# ProPrj_ProDocument_IO_Board_v3_1_2024-08.net
KiCad netlist of a schematic drawn in EasyEDA Pro
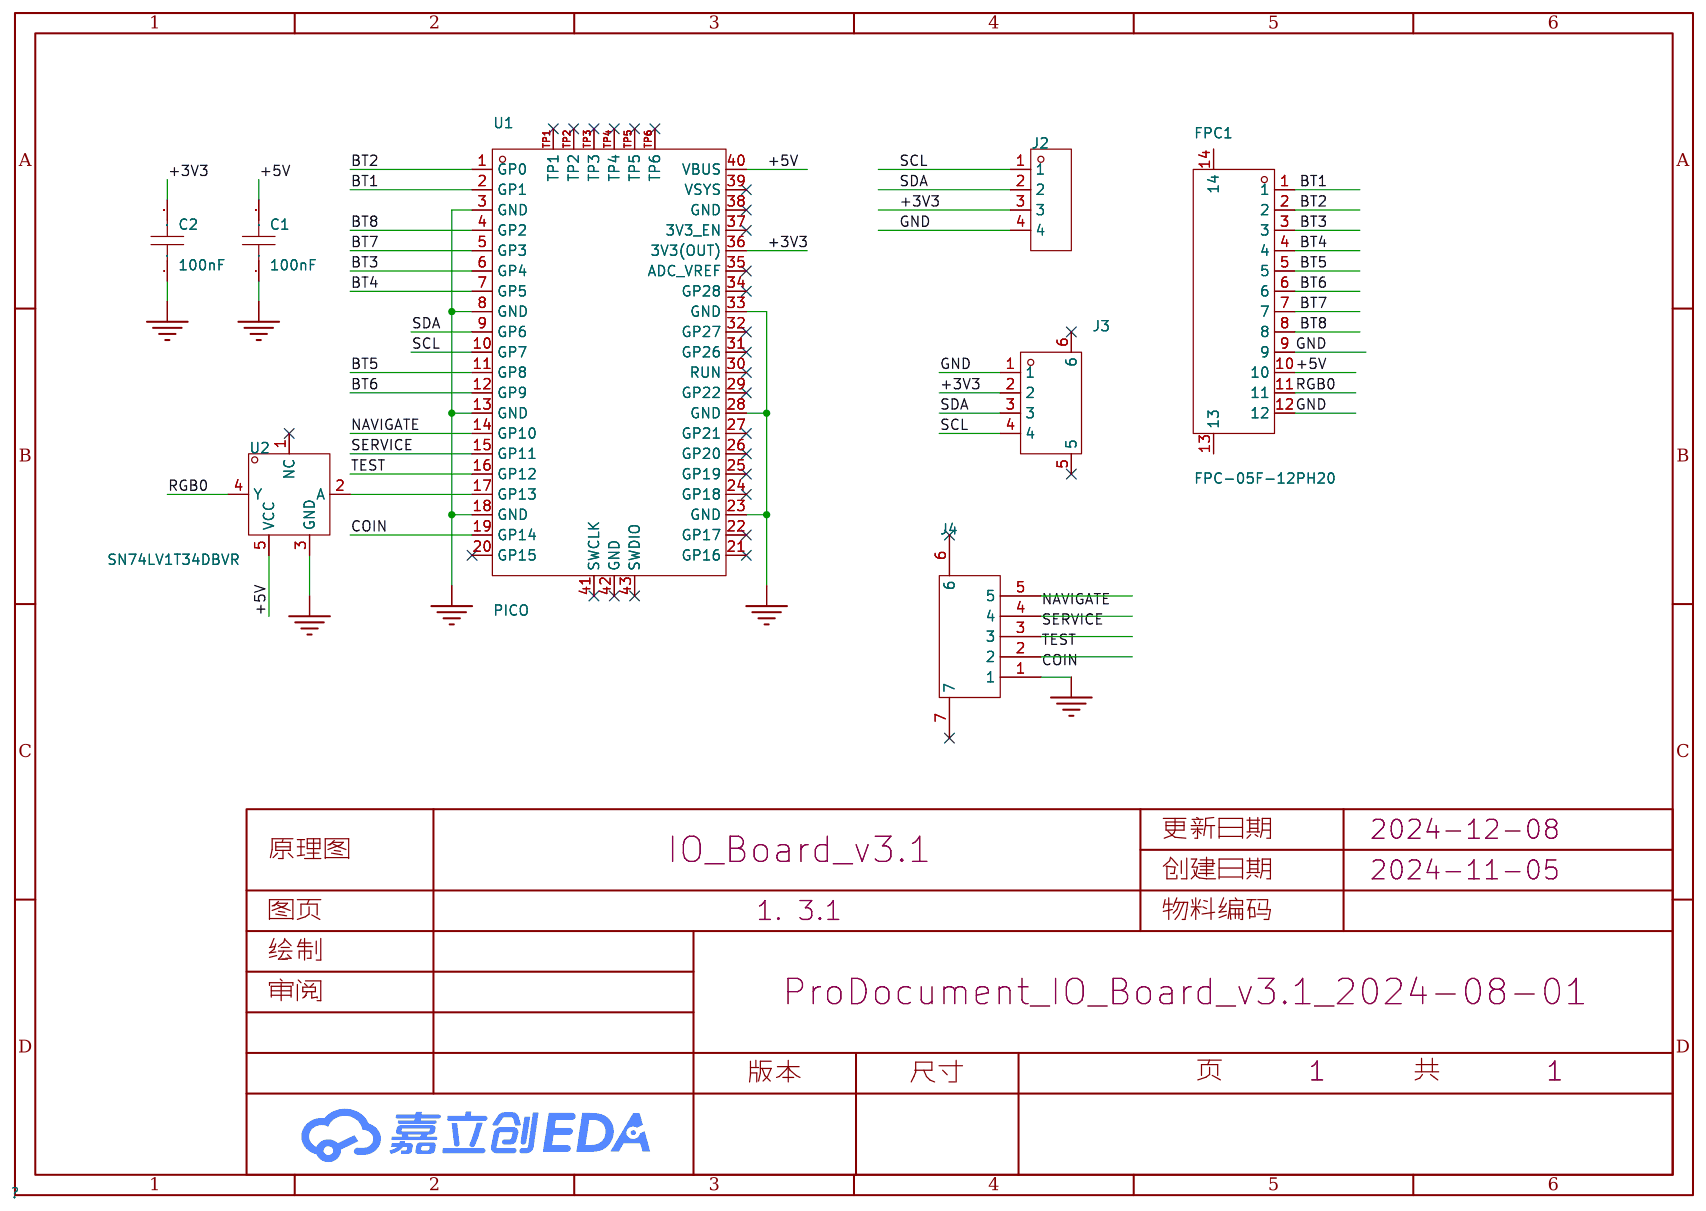
[diagram p0: schematic sheet]

(export (version "E")
  (design (tool "Eeschema 10.0.6"))
  (components
    (comp (ref "C1")
      (value "100nF")
      (footprint "easyedapro:C0603")
      (libsource (lib "easyedapro") (part "CapAcitance"))
    )
    (comp (ref "C2")
      (value "100nF")
      (footprint "easyedapro:C0603")
      (libsource (lib "easyedapro") (part "CapAcitance"))
    )
    (comp (ref "FPC1")
      (value "FPC-05F-12PH20")
      (footprint "easyedapro:FPC-SMD_12P-P0.50_FPC-05F-12PH20")
      (description "锁定特性:翻盖式;触点类型:下接;触点数量:12P;间距:0.5mm;安装类型:卧贴;工作温度范围:-25°C~+85°C;")
      (fields (field (name "Manufacturer") "XUNPU(讯普)"))
      (libsource (lib "easyedapro") (part "FPC-05F-12PH20"))
    )
    (comp (ref "J2")
      (value "F136-1104S3CMUB2")
      (footprint "easyedapro:HDR-SMD_4P-P2.54-V-M-LS5.0")
      (fields (field (name "Manufacturer") "Yxcon(宇熙精密)"))
      (libsource (lib "easyedapro") (part "F136-1104S3CMUB2"))
    )
    (comp (ref "J3")
      (value "AFA01-S04FCA-00")
      (footprint "easyedapro:FPC-SMD_4P-P1.00_JS_AFA01-S04FCA-00")
      (description "锁定特性:翻盖式;触点类型:下接;触点数量:4P;间距:1mm;安装类型:卧贴;工作温度范围:-20°C~+85°C;")
      (fields (field (name "Manufacturer") "JS(钜硕电子)"))
      (libsource (lib "easyedapro") (part "AFA01-S04FCA-00"))
    )
    (comp (ref "J4")
      (value "AFA01-S05FCC-00")
      (footprint "easyedapro:FPC-SMD_P1.00-5P_FGS-XJ-H2.0")
      (description "锁定特性:翻盖式;触点类型:下接;触点数量:5P;间距:1mm;安装类型:卧贴;")
      (fields (field (name "Manufacturer") "JS(钜硕电子)"))
      (libsource (lib "easyedapro") (part "AFA01-S05FCC-00"))
    )
    (comp (ref "U1")
      (value "PICO")
      (footprint "easyedapro:COMM-SMD_L51.0-W21.0-P2.54_SC0916")
      (fields (field (name "Manufacturer") "Raspberry Pi(树莓派)"))
      (libsource (lib "easyedapro") (part "PICO"))
    )
    (comp (ref "U2")
      (value "SN74LV1T34DBVR")
      (footprint "easyedapro:SOT-23-5_L2.9-W1.6-P0.95-LS2.8-BR")
      (description "输入类型:-;电源电压:1.6V~5.5V;元件数:1;每个元件位数:1;灌电流(IOL):8mA;拉电流(IOH):8mA;")
      (fields (field (name "Manufacturer") "TI(德州仪器)"))
      (libsource (lib "easyedapro") (part "SN74LV1T34DBVR"))
    )
  )
  (nets
    (net (code "1") (name "/+3V3") (class "Default")
      (node (ref "C2") (pin "2") (pinfunction "2_2") (pintype "input"))
      (node (ref "J2") (pin "3") (pinfunction "3_3") (pintype "unspecified"))
      (node (ref "J3") (pin "2") (pinfunction "2_2") (pintype "unspecified"))
      (node (ref "U1") (pin "36") (pinfunction "3V3(OUT)_36") (pintype "unspecified"))
    )
    (net (code "2") (name "/+5V") (class "Default")
      (node (ref "C1") (pin "2") (pinfunction "2_2") (pintype "input"))
      (node (ref "FPC1") (pin "10") (pinfunction "10_10") (pintype "unspecified"))
      (node (ref "U1") (pin "40") (pinfunction "VBUS_40") (pintype "unspecified"))
      (node (ref "U2") (pin "5") (pinfunction "VCC_5") (pintype "unspecified"))
    )
    (net (code "3") (name "/BT1") (class "Default")
      (node (ref "FPC1") (pin "1") (pinfunction "1_1") (pintype "unspecified"))
      (node (ref "U1") (pin "2") (pinfunction "GP1_2") (pintype "unspecified"))
    )
    (net (code "4") (name "/BT2") (class "Default")
      (node (ref "FPC1") (pin "2") (pinfunction "2_2") (pintype "unspecified"))
      (node (ref "U1") (pin "1") (pinfunction "GP0_1") (pintype "unspecified"))
    )
    (net (code "5") (name "/BT3") (class "Default")
      (node (ref "FPC1") (pin "3") (pinfunction "3_3") (pintype "unspecified"))
      (node (ref "U1") (pin "6") (pinfunction "GP4_6") (pintype "unspecified"))
    )
    (net (code "6") (name "/BT4") (class "Default")
      (node (ref "FPC1") (pin "4") (pinfunction "4_4") (pintype "unspecified"))
      (node (ref "U1") (pin "7") (pinfunction "GP5_7") (pintype "unspecified"))
    )
    (net (code "7") (name "/BT5") (class "Default")
      (node (ref "FPC1") (pin "5") (pinfunction "5_5") (pintype "unspecified"))
      (node (ref "U1") (pin "11") (pinfunction "GP8_11") (pintype "unspecified"))
    )
    (net (code "8") (name "/BT6") (class "Default")
      (node (ref "FPC1") (pin "6") (pinfunction "6_6") (pintype "unspecified"))
      (node (ref "U1") (pin "12") (pinfunction "GP9_12") (pintype "unspecified"))
    )
    (net (code "9") (name "/BT7") (class "Default")
      (node (ref "FPC1") (pin "7") (pinfunction "7_7") (pintype "unspecified"))
      (node (ref "U1") (pin "5") (pinfunction "GP3_5") (pintype "unspecified"))
    )
    (net (code "10") (name "/BT8") (class "Default")
      (node (ref "FPC1") (pin "8") (pinfunction "8_8") (pintype "unspecified"))
      (node (ref "U1") (pin "4") (pinfunction "GP2_4") (pintype "unspecified"))
    )
    (net (code "11") (name "/COIN") (class "Default")
      (node (ref "J4") (pin "2") (pinfunction "2_2") (pintype "unspecified"))
      (node (ref "U1") (pin "19") (pinfunction "GP14_19") (pintype "unspecified"))
    )
    (net (code "12") (name "/NAVIGATE") (class "Default")
      (node (ref "J4") (pin "5") (pinfunction "5_5") (pintype "unspecified"))
      (node (ref "U1") (pin "14") (pinfunction "GP10_14") (pintype "unspecified"))
    )
    (net (code "13") (name "/RGB0") (class "Default")
      (node (ref "FPC1") (pin "11") (pinfunction "11_11") (pintype "unspecified"))
      (node (ref "U2") (pin "4") (pinfunction "Y_4") (pintype "unspecified"))
    )
    (net (code "14") (name "/SCL") (class "Default")
      (node (ref "J2") (pin "1") (pinfunction "1_1") (pintype "unspecified"))
      (node (ref "J3") (pin "4") (pinfunction "4_4") (pintype "unspecified"))
      (node (ref "U1") (pin "10") (pinfunction "GP7_10") (pintype "unspecified"))
    )
    (net (code "15") (name "/SDA") (class "Default")
      (node (ref "J2") (pin "2") (pinfunction "2_2") (pintype "unspecified"))
      (node (ref "J3") (pin "3") (pinfunction "3_3") (pintype "unspecified"))
      (node (ref "U1") (pin "9") (pinfunction "GP6_9") (pintype "unspecified"))
    )
    (net (code "16") (name "/SERVICE") (class "Default")
      (node (ref "J4") (pin "4") (pinfunction "4_4") (pintype "unspecified"))
      (node (ref "U1") (pin "15") (pinfunction "GP11_15") (pintype "unspecified"))
    )
    (net (code "17") (name "/TEST") (class "Default")
      (node (ref "J4") (pin "3") (pinfunction "3_3") (pintype "unspecified"))
      (node (ref "U1") (pin "16") (pinfunction "GP12_16") (pintype "unspecified"))
    )
    (net (code "18") (name "GND") (class "Default")
      (node (ref "C1") (pin "1") (pinfunction "1_1") (pintype "input"))
      (node (ref "C2") (pin "1") (pinfunction "1_1") (pintype "input"))
      (node (ref "FPC1") (pin "12") (pinfunction "12_12") (pintype "unspecified"))
      (node (ref "FPC1") (pin "9") (pinfunction "9_9") (pintype "unspecified"))
      (node (ref "J2") (pin "4") (pinfunction "4_4") (pintype "unspecified"))
      (node (ref "J3") (pin "1") (pinfunction "1_1") (pintype "unspecified"))
      (node (ref "J4") (pin "1") (pinfunction "1_1") (pintype "unspecified"))
      (node (ref "U1") (pin "13") (pinfunction "GND_13") (pintype "unspecified"))
      (node (ref "U1") (pin "18") (pinfunction "GND_18") (pintype "unspecified"))
      (node (ref "U1") (pin "23") (pinfunction "GND_23") (pintype "unspecified"))
      (node (ref "U1") (pin "28") (pinfunction "GND_28") (pintype "unspecified"))
      (node (ref "U1") (pin "3") (pinfunction "GND_3") (pintype "unspecified"))
      (node (ref "U1") (pin "33") (pinfunction "GND_33") (pintype "unspecified"))
      (node (ref "U1") (pin "8") (pinfunction "GND_8") (pintype "unspecified"))
      (node (ref "U2") (pin "3") (pinfunction "GND_3") (pintype "unspecified"))
    )
    (net (code "19") (name "Net-(U1-GP13)") (class "Default")
      (node (ref "U1") (pin "17") (pinfunction "GP13_17") (pintype "unspecified"))
      (node (ref "U2") (pin "2") (pinfunction "A_2") (pintype "unspecified"))
    )
    (net (code "20") (name "unconnected-(FPC1-Pad13)") (class "Default")
      (node (ref "FPC1") (pin "13") (pinfunction "13_13") (pintype "unspecified"))
    )
    (net (code "21") (name "unconnected-(FPC1-Pad14)") (class "Default")
      (node (ref "FPC1") (pin "14") (pinfunction "14_14") (pintype "unspecified"))
    )
    (net (code "22") (name "unconnected-(J3-Pad5)") (class "Default")
      (node (ref "J3") (pin "5") (pinfunction "5_5") (pintype "unspecified+no_connect"))
    )
    (net (code "23") (name "unconnected-(J3-Pad6)") (class "Default")
      (node (ref "J3") (pin "6") (pinfunction "6_6") (pintype "unspecified+no_connect"))
    )
    (net (code "24") (name "unconnected-(J4-Pad6)") (class "Default")
      (node (ref "J4") (pin "6") (pinfunction "6_6") (pintype "unspecified+no_connect"))
    )
    (net (code "25") (name "unconnected-(J4-Pad7)") (class "Default")
      (node (ref "J4") (pin "7") (pinfunction "7_7") (pintype "unspecified+no_connect"))
    )
    (net (code "26") (name "unconnected-(U1-3V3_EN-Pad37)") (class "Default")
      (node (ref "U1") (pin "37") (pinfunction "3V3_EN_37") (pintype "unspecified+no_connect"))
    )
    (net (code "27") (name "unconnected-(U1-ADC_VREF-Pad35)") (class "Default")
      (node (ref "U1") (pin "35") (pinfunction "ADC_VREF_35") (pintype "unspecified+no_connect"))
    )
    (net (code "28") (name "unconnected-(U1-GND-Pad38)") (class "Default")
      (node (ref "U1") (pin "38") (pinfunction "GND_38") (pintype "unspecified+no_connect"))
    )
    (net (code "29") (name "unconnected-(U1-GND-Pad42)") (class "Default")
      (node (ref "U1") (pin "42") (pinfunction "GND_42") (pintype "unspecified+no_connect"))
    )
    (net (code "30") (name "unconnected-(U1-GP15-Pad20)") (class "Default")
      (node (ref "U1") (pin "20") (pinfunction "GP15_20") (pintype "unspecified+no_connect"))
    )
    (net (code "31") (name "unconnected-(U1-GP16-Pad21)") (class "Default")
      (node (ref "U1") (pin "21") (pinfunction "GP16_21") (pintype "unspecified+no_connect"))
    )
    (net (code "32") (name "unconnected-(U1-GP17-Pad22)") (class "Default")
      (node (ref "U1") (pin "22") (pinfunction "GP17_22") (pintype "unspecified+no_connect"))
    )
    (net (code "33") (name "unconnected-(U1-GP18-Pad24)") (class "Default")
      (node (ref "U1") (pin "24") (pinfunction "GP18_24") (pintype "unspecified+no_connect"))
    )
    (net (code "34") (name "unconnected-(U1-GP19-Pad25)") (class "Default")
      (node (ref "U1") (pin "25") (pinfunction "GP19_25") (pintype "unspecified+no_connect"))
    )
    (net (code "35") (name "unconnected-(U1-GP20-Pad26)") (class "Default")
      (node (ref "U1") (pin "26") (pinfunction "GP20_26") (pintype "unspecified+no_connect"))
    )
    (net (code "36") (name "unconnected-(U1-GP21-Pad27)") (class "Default")
      (node (ref "U1") (pin "27") (pinfunction "GP21_27") (pintype "unspecified+no_connect"))
    )
    (net (code "37") (name "unconnected-(U1-GP22-Pad29)") (class "Default")
      (node (ref "U1") (pin "29") (pinfunction "GP22_29") (pintype "unspecified+no_connect"))
    )
    (net (code "38") (name "unconnected-(U1-GP26-Pad31)") (class "Default")
      (node (ref "U1") (pin "31") (pinfunction "GP26_31") (pintype "unspecified+no_connect"))
    )
    (net (code "39") (name "unconnected-(U1-GP27-Pad32)") (class "Default")
      (node (ref "U1") (pin "32") (pinfunction "GP27_32") (pintype "unspecified+no_connect"))
    )
    (net (code "40") (name "unconnected-(U1-GP28-Pad34)") (class "Default")
      (node (ref "U1") (pin "34") (pinfunction "GP28_34") (pintype "unspecified+no_connect"))
    )
    (net (code "41") (name "unconnected-(U1-PadTP1)") (class "Default")
      (node (ref "U1") (pin "TP1") (pinfunction "TP1_TP1") (pintype "unspecified+no_connect"))
    )
    (net (code "42") (name "unconnected-(U1-PadTP2)") (class "Default")
      (node (ref "U1") (pin "TP2") (pinfunction "TP2_TP2") (pintype "unspecified+no_connect"))
    )
    (net (code "43") (name "unconnected-(U1-PadTP3)") (class "Default")
      (node (ref "U1") (pin "TP3") (pinfunction "TP3_TP3") (pintype "unspecified+no_connect"))
    )
    (net (code "44") (name "unconnected-(U1-PadTP4)") (class "Default")
      (node (ref "U1") (pin "TP4") (pinfunction "TP4_TP4") (pintype "unspecified+no_connect"))
    )
    (net (code "45") (name "unconnected-(U1-PadTP5)") (class "Default")
      (node (ref "U1") (pin "TP5") (pinfunction "TP5_TP5") (pintype "unspecified+no_connect"))
    )
    (net (code "46") (name "unconnected-(U1-PadTP6)") (class "Default")
      (node (ref "U1") (pin "TP6") (pinfunction "TP6_TP6") (pintype "unspecified+no_connect"))
    )
    (net (code "47") (name "unconnected-(U1-RUN-Pad30)") (class "Default")
      (node (ref "U1") (pin "30") (pinfunction "RUN_30") (pintype "unspecified+no_connect"))
    )
    (net (code "48") (name "unconnected-(U1-SWCLK-Pad41)") (class "Default")
      (node (ref "U1") (pin "41") (pinfunction "SWCLK_41") (pintype "unspecified+no_connect"))
    )
    (net (code "49") (name "unconnected-(U1-SWDIO-Pad43)") (class "Default")
      (node (ref "U1") (pin "43") (pinfunction "SWDIO_43") (pintype "unspecified+no_connect"))
    )
    (net (code "50") (name "unconnected-(U1-VSYS-Pad39)") (class "Default")
      (node (ref "U1") (pin "39") (pinfunction "VSYS_39") (pintype "unspecified+no_connect"))
    )
    (net (code "51") (name "unconnected-(U2-NC-Pad1)") (class "Default")
      (node (ref "U2") (pin "1") (pinfunction "NC_1") (pintype "unspecified+no_connect"))
    )
  )
)
